# VISUR-botI_a.net
KiCad netlist of a schematic drawn in Altium Designer
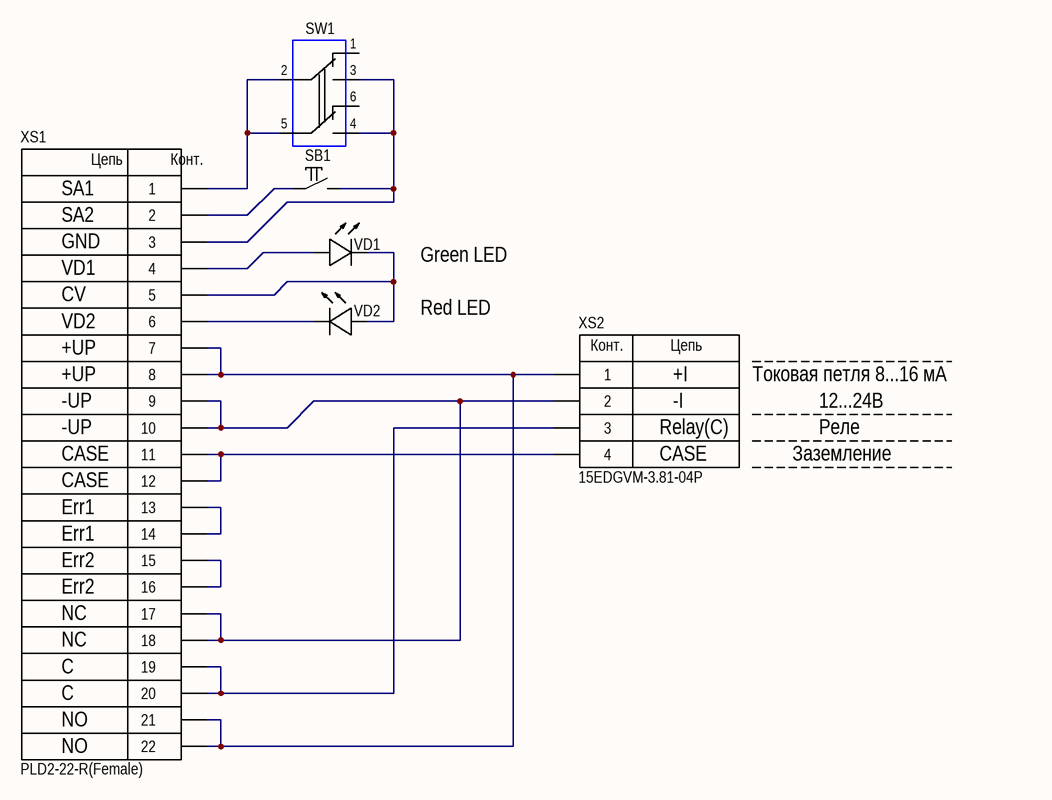
[diagram p0: VISUR-botI_a.SchDoc]

(export (version "E")
  (design (tool "Eeschema 10.0.6"))
  (components
    (comp (ref "SB1")
      (value "~")
      (footprint "BUT: 6x6")
      (fields
        (field (name "MANUFACTURER") "TE Connectivity")
        (field (name "VALUEMANUFACTURERPARTNUMBER") "Tactile button, 6x6mm")
        (field (name "PARTNUMBER") "FSM2JSMAATR")
      )
      (libsource (lib "electromechanics") (part "Button_tactile"))
    )
    (comp (ref "SW1")
      (value "JS202011SCQN")
      (footprint "JS202011CQN")
      (description "Переключатель")
      (fields
        (field (name "MANUFACTURER") "C&K Component")
        (field (name "REPLACEMENTPART1PARTNUMBER") "is-1390")
      )
      (libsource (lib "Switch") (part "JS202011SCQN"))
    )
    (comp (ref "VD1")
      (value "KM2520SURCK09")
      (footprint "KM2520SURCK09")
      (description "LED")
      (libsource (lib "Kingbright LED") (part "KM2520SURCK09"))
    )
    (comp (ref "VD2")
      (value "KM2520SURCK09")
      (footprint "KM2520SURCK09")
      (description "LED")
      (libsource (lib "Kingbright LED") (part "KM2520SURCK09"))
    )
    (comp (ref "XS1")
      (value "PLD2-22-R(Female)")
      (footprint "CON: PLD2-22-R(Female)")
      (libsource (lib "connector") (part "PLD2-22(Female)"))
    )
    (comp (ref "XS2")
      (value "15EDGVM-3.81-04P")
      (footprint "CON: 15EDGVM-3.81-04P")
      (libsource (lib "connector") (part "15EDGVM-3.81-04P"))
    )
  )
  (nets
    (net (code "1") (name "Net-(SB1-Pad1)") (class "Default")
      (node (ref "SB1") (pin "1") (pinfunction "1_1") (pintype "passive"))
      (node (ref "XS1") (pin "2") (pinfunction "2_2") (pintype "passive"))
    )
    (net (code "2") (name "Net-(SB1-Pad2)") (class "Default")
      (node (ref "SB1") (pin "2") (pinfunction "2_2") (pintype "passive"))
      (node (ref "SW1") (pin "3") (pinfunction "3_3") (pintype "passive"))
      (node (ref "SW1") (pin "4") (pinfunction "4_4") (pintype "passive"))
      (node (ref "XS1") (pin "3") (pinfunction "3_3") (pintype "power_in"))
    )
    (net (code "3") (name "Net-(SW1-Pad2)") (class "Default")
      (node (ref "SW1") (pin "2") (pinfunction "2_2") (pintype "passive"))
      (node (ref "SW1") (pin "5") (pinfunction "5_5") (pintype "passive"))
      (node (ref "XS1") (pin "1") (pinfunction "1_1") (pintype "passive"))
    )
    (net (code "4") (name "Net-(VD1-A)") (class "Default")
      (node (ref "VD1") (pin "1") (pinfunction "A_1") (pintype "passive"))
      (node (ref "XS1") (pin "4") (pinfunction "4_4") (pintype "power_in"))
    )
    (net (code "5") (name "Net-(VD1-K)") (class "Default")
      (node (ref "VD1") (pin "2") (pinfunction "K_2") (pintype "passive"))
      (node (ref "VD2") (pin "1") (pinfunction "A_1") (pintype "passive"))
      (node (ref "XS1") (pin "5") (pinfunction "5_5") (pintype "power_in"))
    )
    (net (code "6") (name "Net-(VD2-K)") (class "Default")
      (node (ref "VD2") (pin "2") (pinfunction "K_2") (pintype "passive"))
      (node (ref "XS1") (pin "6") (pinfunction "6_6") (pintype "power_in"))
    )
    (net (code "7") (name "Net-(XS1-Pad10)") (class "Default")
      (node (ref "XS1") (pin "10") (pinfunction "10_10") (pintype "power_in"))
      (node (ref "XS1") (pin "17") (pinfunction "17_17") (pintype "passive"))
      (node (ref "XS1") (pin "18") (pinfunction "18_18") (pintype "passive"))
      (node (ref "XS1") (pin "9") (pinfunction "9_9") (pintype "power_in"))
      (node (ref "XS2") (pin "2") (pinfunction "2_2") (pintype "passive"))
    )
    (net (code "8") (name "Net-(XS1-Pad11)") (class "Default")
      (node (ref "XS1") (pin "11") (pinfunction "11_11") (pintype "power_in"))
      (node (ref "XS1") (pin "12") (pinfunction "12_12") (pintype "power_in"))
      (node (ref "XS2") (pin "4") (pinfunction "4_4") (pintype "passive"))
    )
    (net (code "9") (name "Net-(XS1-Pad13)") (class "Default")
      (node (ref "XS1") (pin "13") (pinfunction "13_13") (pintype "power_in"))
      (node (ref "XS1") (pin "14") (pinfunction "14_14") (pintype "power_in"))
    )
    (net (code "10") (name "Net-(XS1-Pad15)") (class "Default")
      (node (ref "XS1") (pin "15") (pinfunction "15_15") (pintype "passive"))
      (node (ref "XS1") (pin "16") (pinfunction "16_16") (pintype "passive"))
    )
    (net (code "11") (name "Net-(XS1-Pad19)") (class "Default")
      (node (ref "XS1") (pin "19") (pinfunction "19_19") (pintype "passive"))
      (node (ref "XS1") (pin "20") (pinfunction "20_20") (pintype "passive"))
      (node (ref "XS2") (pin "3") (pinfunction "3_3") (pintype "passive"))
    )
    (net (code "12") (name "Net-(XS1-Pad21)") (class "Default")
      (node (ref "XS1") (pin "21") (pinfunction "21_21") (pintype "passive"))
      (node (ref "XS1") (pin "22") (pinfunction "22_22") (pintype "passive"))
      (node (ref "XS1") (pin "7") (pinfunction "7_7") (pintype "power_in"))
      (node (ref "XS1") (pin "8") (pinfunction "8_8") (pintype "power_in"))
      (node (ref "XS2") (pin "1") (pinfunction "1_1") (pintype "passive"))
    )
    (net (code "13") (name "unconnected-(SW1-Pad1)") (class "Default")
      (node (ref "SW1") (pin "1") (pinfunction "1_1") (pintype "passive"))
    )
    (net (code "14") (name "unconnected-(SW1-Pad6)") (class "Default")
      (node (ref "SW1") (pin "6") (pinfunction "6_6") (pintype "passive"))
    )
  )
)
